# soth-core.net
KiCad netlist of a schematic drawn in EAGLE
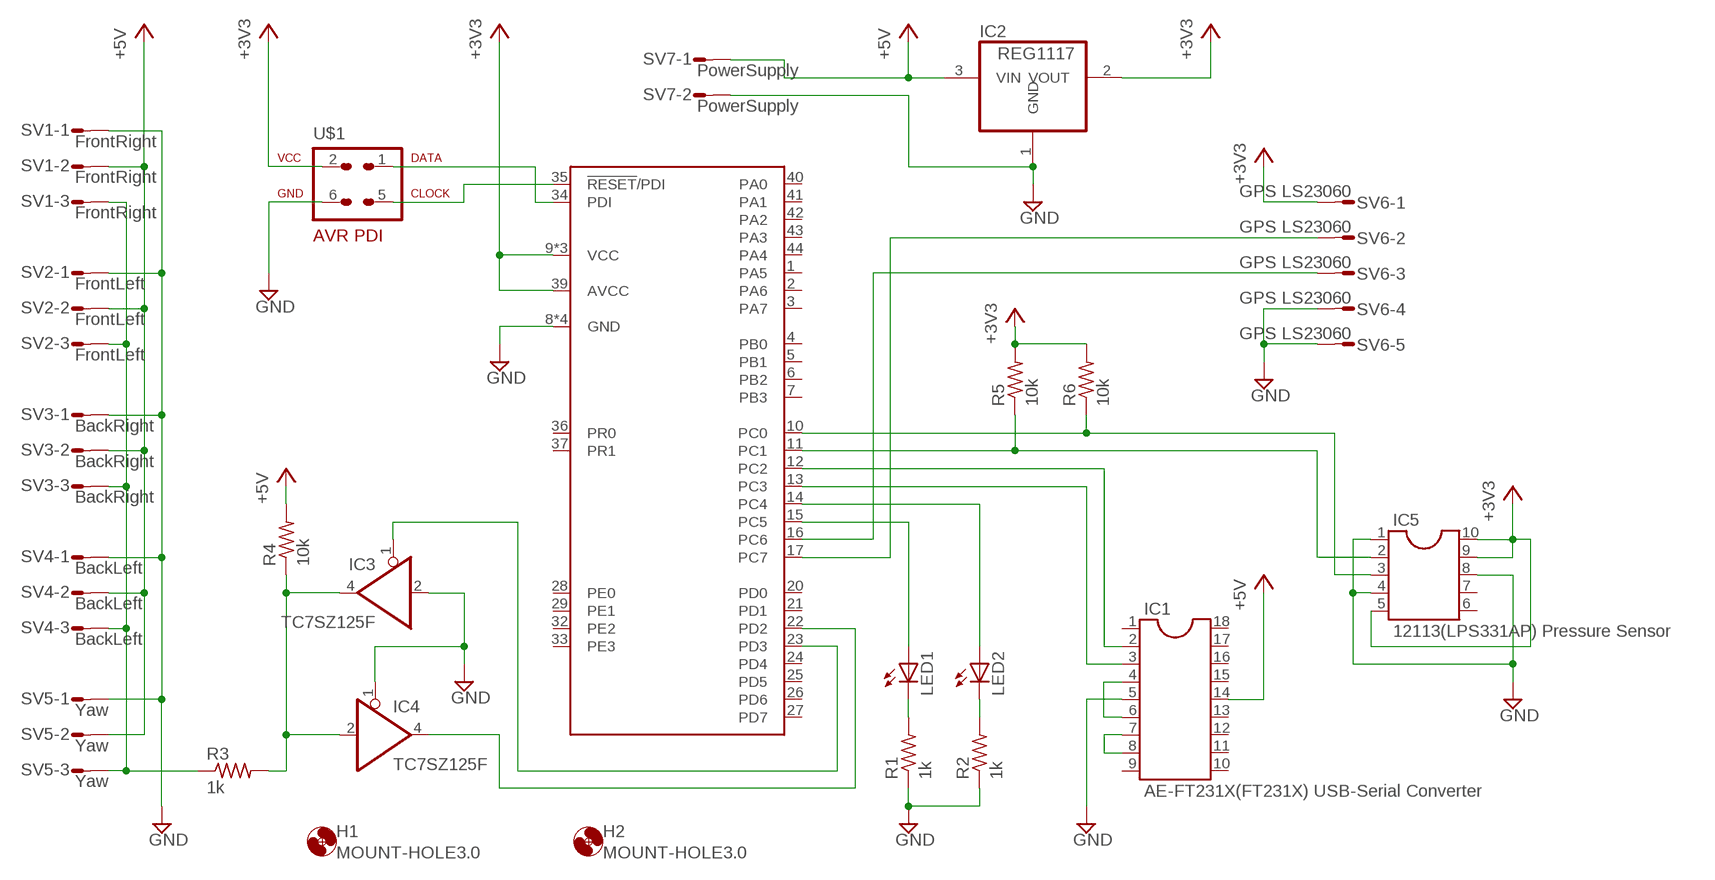
[diagram p0: schematic, sheet 1]

(export (version "E")
  (design (tool "Eeschema 10.0.6"))
  (components
    (comp (ref "H1")
      (value "MOUNT-HOLE3.0")
      (footprint "eagle-import:3,0")
      (libsource (lib "eagle-import") (part "MOUNT-HOLE3.0"))
    )
    (comp (ref "H2")
      (value "MOUNT-HOLE3.0")
      (footprint "eagle-import:3,0")
      (libsource (lib "eagle-import") (part "MOUNT-HOLE3.0"))
    )
    (comp (ref "IC1")
      (value "AE-FT231X(FT231X) USB-Serial Converter")
      (footprint "eagle-import:SOCKET-18")
      (libsource (lib "eagle-import") (part "DIL18S"))
    )
    (comp (ref "IC2")
      (value "REG1117")
      (footprint "eagle-import:SOT223")
      (libsource (lib "eagle-import") (part "REG1117"))
    )
    (comp (ref "IC3")
      (value "TC7SZ125F")
      (footprint "eagle-import:SOT23-5")
      (libsource (lib "eagle-import") (part "741G125DBVAHC"))
    )
    (comp (ref "IC4")
      (value "TC7SZ125F")
      (footprint "eagle-import:SOT23-5")
      (libsource (lib "eagle-import") (part "741G125DBVAHC"))
    )
    (comp (ref "IC5")
      (value "12113(LPS331AP) Pressure Sensor")
      (footprint "eagle-import:DIL10")
      (libsource (lib "eagle-import") (part "DIL10"))
    )
    (comp (ref "LED1")
      (value "LED")
      (footprint "eagle-import:SMARTLED-TTW")
      (libsource (lib "eagle-import") (part "LED"))
    )
    (comp (ref "LED2")
      (value "LED")
      (footprint "eagle-import:SMARTLED-TTW")
      (libsource (lib "eagle-import") (part "LED"))
    )
    (comp (ref "R1")
      (value "1k")
      (footprint "eagle-import:R0805")
      (libsource (lib "eagle-import") (part "R-US_R0805"))
    )
    (comp (ref "R2")
      (value "1k")
      (footprint "eagle-import:R0805")
      (libsource (lib "eagle-import") (part "R-US_R0805"))
    )
    (comp (ref "R3")
      (value "1k")
      (footprint "eagle-import:R0805")
      (libsource (lib "eagle-import") (part "R-US_R0805"))
    )
    (comp (ref "R4")
      (value "10k")
      (footprint "eagle-import:R0805")
      (libsource (lib "eagle-import") (part "R-US_R0805"))
    )
    (comp (ref "R5")
      (value "10k")
      (footprint "eagle-import:R0805")
      (libsource (lib "eagle-import") (part "R-US_R0805"))
    )
    (comp (ref "R6")
      (value "10k")
      (footprint "eagle-import:R0805")
      (libsource (lib "eagle-import") (part "R-US_R0805"))
    )
    (comp (ref "SV1")
      (value "FrontRight")
      (footprint "eagle-import:S03P")
      (libsource (lib "eagle-import") (part "S03P"))
    )
    (comp (ref "SV2")
      (value "FrontLeft")
      (footprint "eagle-import:S03P")
      (libsource (lib "eagle-import") (part "S03P"))
    )
    (comp (ref "SV3")
      (value "BackRight")
      (footprint "eagle-import:S03P")
      (libsource (lib "eagle-import") (part "S03P"))
    )
    (comp (ref "SV4")
      (value "BackLeft")
      (footprint "eagle-import:S03P")
      (libsource (lib "eagle-import") (part "S03P"))
    )
    (comp (ref "SV5")
      (value "Yaw")
      (footprint "eagle-import:S03P")
      (libsource (lib "eagle-import") (part "S03P"))
    )
    (comp (ref "SV6")
      (value "GPS LS23060")
      (footprint "eagle-import:S05P")
      (libsource (lib "eagle-import") (part "S05P"))
    )
    (comp (ref "SV7")
      (value "PowerSupply")
      (footprint "eagle-import:S02P")
      (libsource (lib "eagle-import") (part "S02P"))
    )
    (comp (ref "U$1")
      (value "AVR-PDIVERT")
      (footprint "eagle-import:AVR-ISP-6")
      (libsource (lib "eagle-import") (part "AVR-PDIVERT"))
    )
    (comp (ref "U1")
      (value "ATXMEGA32D4-AU")
      (footprint "eagle-import:TQFP-44A-44")
      (libsource (lib "eagle-import") (part "ATXMEGA32D4-AU"))
    )
  )
  (nets
    (net (code "1") (name "+3V3") (class "Default")
      (node (ref "IC2") (pin "2") (pinfunction "VOUT_2") (pintype "output"))
      (node (ref "IC5") (pin "10") (pinfunction "10_10") (pintype "passive"))
      (node (ref "IC5") (pin "5") (pinfunction "5_5") (pintype "passive"))
      (node (ref "IC5") (pin "9") (pinfunction "9_9") (pintype "passive"))
      (node (ref "R5") (pin "2") (pinfunction "2_2") (pintype "passive"))
      (node (ref "R6") (pin "2") (pinfunction "2_2") (pintype "passive"))
      (node (ref "SV6") (pin "1") (pinfunction "S_1") (pintype "passive"))
      (node (ref "U$1") (pin "2") (pinfunction "2_2") (pintype "passive"))
      (node (ref "U1") (pin "19") (pinfunction "VCC_19") (pintype "power_in"))
      (node (ref "U1") (pin "31") (pinfunction "VCC_31") (pintype "power_in"))
      (node (ref "U1") (pin "39") (pinfunction "AVCC_39") (pintype "power_in"))
      (node (ref "U1") (pin "9") (pinfunction "VCC_9") (pintype "power_in"))
    )
    (net (code "2") (name "+5V") (class "Default")
      (node (ref "IC1") (pin "14") (pinfunction "14_14") (pintype "passive"))
      (node (ref "IC2") (pin "3") (pinfunction "VIN_3") (pintype "input"))
      (node (ref "R4") (pin "2") (pinfunction "2_2") (pintype "passive"))
      (node (ref "SV1") (pin "2") (pinfunction "S_2") (pintype "passive"))
      (node (ref "SV2") (pin "2") (pinfunction "S_2") (pintype "passive"))
      (node (ref "SV3") (pin "2") (pinfunction "S_2") (pintype "passive"))
      (node (ref "SV4") (pin "2") (pinfunction "S_2") (pintype "passive"))
      (node (ref "SV5") (pin "2") (pinfunction "S_2") (pintype "passive"))
      (node (ref "SV7") (pin "1") (pinfunction "S_1") (pintype "passive"))
    )
    (net (code "3") (name "GND") (class "Default")
      (node (ref "IC1") (pin "5") (pinfunction "5_5") (pintype "passive"))
      (node (ref "IC2") (pin "1") (pinfunction "GND_1") (pintype "power_in"))
      (node (ref "IC3") (pin "2") (pinfunction "I_2") (pintype "input"))
      (node (ref "IC4") (pin "1") (pinfunction "OE_1") (pintype "input"))
      (node (ref "IC5") (pin "1") (pinfunction "1_1") (pintype "passive"))
      (node (ref "IC5") (pin "4") (pinfunction "4_4") (pintype "passive"))
      (node (ref "IC5") (pin "8") (pinfunction "8_8") (pintype "passive"))
      (node (ref "R1") (pin "1") (pinfunction "1_1") (pintype "passive"))
      (node (ref "R2") (pin "1") (pinfunction "1_1") (pintype "passive"))
      (node (ref "SV1") (pin "1") (pinfunction "S_1") (pintype "passive"))
      (node (ref "SV2") (pin "1") (pinfunction "S_1") (pintype "passive"))
      (node (ref "SV3") (pin "1") (pinfunction "S_1") (pintype "passive"))
      (node (ref "SV4") (pin "1") (pinfunction "S_1") (pintype "passive"))
      (node (ref "SV5") (pin "1") (pinfunction "S_1") (pintype "passive"))
      (node (ref "SV6") (pin "4") (pinfunction "S_4") (pintype "passive"))
      (node (ref "SV6") (pin "5") (pinfunction "S_5") (pintype "passive"))
      (node (ref "SV7") (pin "2") (pinfunction "S_2") (pintype "passive"))
      (node (ref "U$1") (pin "6") (pinfunction "6_6") (pintype "passive"))
      (node (ref "U1") (pin "18") (pinfunction "GND_18") (pintype "power_in"))
      (node (ref "U1") (pin "30") (pinfunction "GND_30") (pintype "power_in"))
      (node (ref "U1") (pin "38") (pinfunction "GND_38") (pintype "power_in"))
      (node (ref "U1") (pin "8") (pinfunction "GND_8") (pintype "power_in"))
    )
    (net (code "4") (name "Net-(IC1-Pad4)") (class "Default")
      (node (ref "IC1") (pin "4") (pinfunction "4_4") (pintype "passive"))
      (node (ref "IC1") (pin "6") (pinfunction "6_6") (pintype "passive"))
    )
    (net (code "5") (name "Net-(IC1-Pad7)") (class "Default")
      (node (ref "IC1") (pin "7") (pinfunction "7_7") (pintype "passive"))
      (node (ref "IC1") (pin "8") (pinfunction "8_8") (pintype "passive"))
    )
    (net (code "6") (name "Net-(IC3A-O)") (class "Default")
      (node (ref "IC3") (pin "4") (pinfunction "O_4") (pintype "tri_state"))
      (node (ref "IC4") (pin "2") (pinfunction "I_2") (pintype "input"))
      (node (ref "R3") (pin "2") (pinfunction "2_2") (pintype "passive"))
      (node (ref "R4") (pin "1") (pinfunction "1_1") (pintype "passive"))
    )
    (net (code "7") (name "Net-(IC3A-OE)") (class "Default")
      (node (ref "IC3") (pin "1") (pinfunction "OE_1") (pintype "input"))
      (node (ref "U1") (pin "23") (pinfunction "PD3_23") (pintype "bidirectional"))
    )
    (net (code "8") (name "Net-(IC4A-O)") (class "Default")
      (node (ref "IC4") (pin "4") (pinfunction "O_4") (pintype "tri_state"))
      (node (ref "U1") (pin "22") (pinfunction "PD2_22") (pintype "bidirectional"))
    )
    (net (code "9") (name "Net-(LED1-A)") (class "Default")
      (node (ref "LED1") (pin "A@1") (pinfunction "A_A@1") (pintype "passive"))
      (node (ref "U1") (pin "15") (pinfunction "PC5_15") (pintype "bidirectional"))
    )
    (net (code "10") (name "Net-(LED1-C)") (class "Default")
      (node (ref "LED1") (pin "C@1") (pinfunction "C_C@1") (pintype "passive"))
      (node (ref "R1") (pin "2") (pinfunction "2_2") (pintype "passive"))
    )
    (net (code "11") (name "Net-(LED2-A)") (class "Default")
      (node (ref "LED2") (pin "A@1") (pinfunction "A_A@1") (pintype "passive"))
      (node (ref "U1") (pin "14") (pinfunction "PC4_14") (pintype "bidirectional"))
    )
    (net (code "12") (name "Net-(LED2-C)") (class "Default")
      (node (ref "LED2") (pin "C@1") (pinfunction "C_C@1") (pintype "passive"))
      (node (ref "R2") (pin "2") (pinfunction "2_2") (pintype "passive"))
    )
    (net (code "13") (name "Net-(SV1C-S)") (class "Default")
      (node (ref "R3") (pin "1") (pinfunction "1_1") (pintype "passive"))
      (node (ref "SV1") (pin "3") (pinfunction "S_3") (pintype "passive"))
      (node (ref "SV2") (pin "3") (pinfunction "S_3") (pintype "passive"))
      (node (ref "SV3") (pin "3") (pinfunction "S_3") (pintype "passive"))
      (node (ref "SV4") (pin "3") (pinfunction "S_3") (pintype "passive"))
      (node (ref "SV5") (pin "3") (pinfunction "S_3") (pintype "passive"))
    )
    (net (code "14") (name "Net-(SV6B-S)") (class "Default")
      (node (ref "SV6") (pin "2") (pinfunction "S_2") (pintype "passive"))
      (node (ref "U1") (pin "17") (pinfunction "PC7_17") (pintype "bidirectional"))
    )
    (net (code "15") (name "Net-(SV6C-S)") (class "Default")
      (node (ref "SV6") (pin "3") (pinfunction "S_3") (pintype "passive"))
      (node (ref "U1") (pin "16") (pinfunction "PC6_16") (pintype "bidirectional"))
    )
    (net (code "16") (name "Net-(U1-PC0)") (class "Default")
      (node (ref "IC5") (pin "3") (pinfunction "3_3") (pintype "passive"))
      (node (ref "R6") (pin "1") (pinfunction "1_1") (pintype "passive"))
      (node (ref "U1") (pin "10") (pinfunction "PC0_10") (pintype "bidirectional"))
    )
    (net (code "17") (name "Net-(U1-PC1)") (class "Default")
      (node (ref "IC5") (pin "2") (pinfunction "2_2") (pintype "passive"))
      (node (ref "R5") (pin "1") (pinfunction "1_1") (pintype "passive"))
      (node (ref "U1") (pin "11") (pinfunction "PC1_11") (pintype "bidirectional"))
    )
    (net (code "18") (name "Net-(U1-PC2)") (class "Default")
      (node (ref "IC1") (pin "2") (pinfunction "2_2") (pintype "passive"))
      (node (ref "U1") (pin "12") (pinfunction "PC2_12") (pintype "bidirectional"))
    )
    (net (code "19") (name "Net-(U1-PC3)") (class "Default")
      (node (ref "IC1") (pin "3") (pinfunction "3_3") (pintype "passive"))
      (node (ref "U1") (pin "13") (pinfunction "PC3_13") (pintype "bidirectional"))
    )
    (net (code "20") (name "Net-(U1-PDI)") (class "Default")
      (node (ref "U$1") (pin "1") (pinfunction "1_1") (pintype "passive"))
      (node (ref "U1") (pin "34") (pinfunction "PDI_34") (pintype "bidirectional"))
    )
    (net (code "21") (name "Net-(U1-~{RESET}{slash}PDI)") (class "Default")
      (node (ref "U$1") (pin "5") (pinfunction "5_5") (pintype "passive"))
      (node (ref "U1") (pin "35") (pinfunction "~{RESET}/PDI_35") (pintype "bidirectional"))
    )
    (net (code "22") (name "unconnected-(IC1-Pad1)") (class "Default")
      (node (ref "IC1") (pin "1") (pinfunction "1_1") (pintype "passive"))
    )
    (net (code "23") (name "unconnected-(IC1-Pad9)") (class "Default")
      (node (ref "IC1") (pin "9") (pinfunction "9_9") (pintype "passive"))
    )
    (net (code "24") (name "unconnected-(IC1-Pad10)") (class "Default")
      (node (ref "IC1") (pin "10") (pinfunction "10_10") (pintype "passive"))
    )
    (net (code "25") (name "unconnected-(IC1-Pad11)") (class "Default")
      (node (ref "IC1") (pin "11") (pinfunction "11_11") (pintype "passive"))
    )
    (net (code "26") (name "unconnected-(IC1-Pad12)") (class "Default")
      (node (ref "IC1") (pin "12") (pinfunction "12_12") (pintype "passive"))
    )
    (net (code "27") (name "unconnected-(IC1-Pad13)") (class "Default")
      (node (ref "IC1") (pin "13") (pinfunction "13_13") (pintype "passive"))
    )
    (net (code "28") (name "unconnected-(IC1-Pad15)") (class "Default")
      (node (ref "IC1") (pin "15") (pinfunction "15_15") (pintype "passive"))
    )
    (net (code "29") (name "unconnected-(IC1-Pad16)") (class "Default")
      (node (ref "IC1") (pin "16") (pinfunction "16_16") (pintype "passive"))
    )
    (net (code "30") (name "unconnected-(IC1-Pad17)") (class "Default")
      (node (ref "IC1") (pin "17") (pinfunction "17_17") (pintype "passive"))
    )
    (net (code "31") (name "unconnected-(IC1-Pad18)") (class "Default")
      (node (ref "IC1") (pin "18") (pinfunction "18_18") (pintype "passive"))
    )
    (net (code "32") (name "unconnected-(IC5-Pad6)") (class "Default")
      (node (ref "IC5") (pin "6") (pinfunction "6_6") (pintype "passive"))
    )
    (net (code "33") (name "unconnected-(IC5-Pad7)") (class "Default")
      (node (ref "IC5") (pin "7") (pinfunction "7_7") (pintype "passive"))
    )
    (net (code "34") (name "unconnected-(U1-PA0-Pad40)") (class "Default")
      (node (ref "U1") (pin "40") (pinfunction "PA0_40") (pintype "bidirectional"))
    )
    (net (code "35") (name "unconnected-(U1-PA1-Pad41)") (class "Default")
      (node (ref "U1") (pin "41") (pinfunction "PA1_41") (pintype "bidirectional"))
    )
    (net (code "36") (name "unconnected-(U1-PA2-Pad42)") (class "Default")
      (node (ref "U1") (pin "42") (pinfunction "PA2_42") (pintype "bidirectional"))
    )
    (net (code "37") (name "unconnected-(U1-PA3-Pad43)") (class "Default")
      (node (ref "U1") (pin "43") (pinfunction "PA3_43") (pintype "bidirectional"))
    )
    (net (code "38") (name "unconnected-(U1-PA4-Pad44)") (class "Default")
      (node (ref "U1") (pin "44") (pinfunction "PA4_44") (pintype "bidirectional"))
    )
    (net (code "39") (name "unconnected-(U1-PA5-Pad1)") (class "Default")
      (node (ref "U1") (pin "1") (pinfunction "PA5_1") (pintype "bidirectional"))
    )
    (net (code "40") (name "unconnected-(U1-PA6-Pad2)") (class "Default")
      (node (ref "U1") (pin "2") (pinfunction "PA6_2") (pintype "bidirectional"))
    )
    (net (code "41") (name "unconnected-(U1-PA7-Pad3)") (class "Default")
      (node (ref "U1") (pin "3") (pinfunction "PA7_3") (pintype "bidirectional"))
    )
    (net (code "42") (name "unconnected-(U1-PB0-Pad4)") (class "Default")
      (node (ref "U1") (pin "4") (pinfunction "PB0_4") (pintype "bidirectional"))
    )
    (net (code "43") (name "unconnected-(U1-PB1-Pad5)") (class "Default")
      (node (ref "U1") (pin "5") (pinfunction "PB1_5") (pintype "bidirectional"))
    )
    (net (code "44") (name "unconnected-(U1-PB2-Pad6)") (class "Default")
      (node (ref "U1") (pin "6") (pinfunction "PB2_6") (pintype "bidirectional"))
    )
    (net (code "45") (name "unconnected-(U1-PB3-Pad7)") (class "Default")
      (node (ref "U1") (pin "7") (pinfunction "PB3_7") (pintype "bidirectional"))
    )
    (net (code "46") (name "unconnected-(U1-PD0-Pad20)") (class "Default")
      (node (ref "U1") (pin "20") (pinfunction "PD0_20") (pintype "bidirectional"))
    )
    (net (code "47") (name "unconnected-(U1-PD1-Pad21)") (class "Default")
      (node (ref "U1") (pin "21") (pinfunction "PD1_21") (pintype "bidirectional"))
    )
    (net (code "48") (name "unconnected-(U1-PD4-Pad24)") (class "Default")
      (node (ref "U1") (pin "24") (pinfunction "PD4_24") (pintype "bidirectional"))
    )
    (net (code "49") (name "unconnected-(U1-PD5-Pad25)") (class "Default")
      (node (ref "U1") (pin "25") (pinfunction "PD5_25") (pintype "bidirectional"))
    )
    (net (code "50") (name "unconnected-(U1-PD6-Pad26)") (class "Default")
      (node (ref "U1") (pin "26") (pinfunction "PD6_26") (pintype "bidirectional"))
    )
    (net (code "51") (name "unconnected-(U1-PD7-Pad27)") (class "Default")
      (node (ref "U1") (pin "27") (pinfunction "PD7_27") (pintype "bidirectional"))
    )
    (net (code "52") (name "unconnected-(U1-PE0-Pad28)") (class "Default")
      (node (ref "U1") (pin "28") (pinfunction "PE0_28") (pintype "bidirectional"))
    )
    (net (code "53") (name "unconnected-(U1-PE1-Pad29)") (class "Default")
      (node (ref "U1") (pin "29") (pinfunction "PE1_29") (pintype "bidirectional"))
    )
    (net (code "54") (name "unconnected-(U1-PE2-Pad32)") (class "Default")
      (node (ref "U1") (pin "32") (pinfunction "PE2_32") (pintype "bidirectional"))
    )
    (net (code "55") (name "unconnected-(U1-PE3-Pad33)") (class "Default")
      (node (ref "U1") (pin "33") (pinfunction "PE3_33") (pintype "bidirectional"))
    )
    (net (code "56") (name "unconnected-(U1-PR0-Pad36)") (class "Default")
      (node (ref "U1") (pin "36") (pinfunction "PR0_36") (pintype "bidirectional"))
    )
    (net (code "57") (name "unconnected-(U1-PR1-Pad37)") (class "Default")
      (node (ref "U1") (pin "37") (pinfunction "PR1_37") (pintype "bidirectional"))
    )
  )
)
